# 9_USART_schdoc.net
KiCad netlist of a schematic drawn in Altium Designer
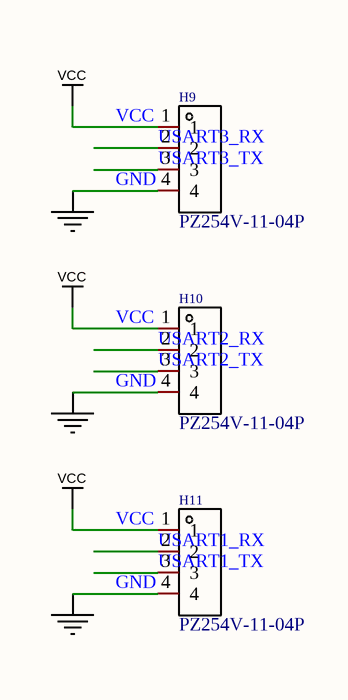
[diagram p0: 9_USART.schdoc.schdoc]

(export (version "E")
  (design (tool "Eeschema 10.0.6"))
  (components
    (comp (ref "H9")
      (value "PZ254V-11-04P")
      (fields (field (name "NAME") "PZ254V-11-04P") (field (name "MANUFACTURER") "XFCN(兴飞)"))
      (libsource (lib "altium-import") (part "root_0_PZ254V-11-04P_"))
    )
    (comp (ref "H10")
      (value "PZ254V-11-04P")
      (fields (field (name "NAME") "PZ254V-11-04P") (field (name "MANUFACTURER") "XFCN(兴飞)"))
      (libsource (lib "altium-import") (part "root_0_PZ254V-11-04P_"))
    )
    (comp (ref "H11")
      (value "PZ254V-11-04P")
      (fields (field (name "NAME") "PZ254V-11-04P") (field (name "MANUFACTURER") "XFCN(兴飞)"))
      (libsource (lib "altium-import") (part "root_0_PZ254V-11-04P_"))
    )
  )
  (nets
    (net (code "1") (name "/GND") (class "Default")
      (node (ref "H10") (pin "4") (pinfunction "4_4") (pintype "passive"))
      (node (ref "H11") (pin "4") (pinfunction "4_4") (pintype "passive"))
      (node (ref "H9") (pin "4") (pinfunction "4_4") (pintype "passive"))
    )
    (net (code "2") (name "/USART1_RX") (class "Default")
      (node (ref "H11") (pin "2") (pinfunction "2_2") (pintype "passive"))
    )
    (net (code "3") (name "/USART1_TX") (class "Default")
      (node (ref "H11") (pin "3") (pinfunction "3_3") (pintype "passive"))
    )
    (net (code "4") (name "/USART2_RX") (class "Default")
      (node (ref "H10") (pin "2") (pinfunction "2_2") (pintype "passive"))
    )
    (net (code "5") (name "/USART2_TX") (class "Default")
      (node (ref "H10") (pin "3") (pinfunction "3_3") (pintype "passive"))
    )
    (net (code "6") (name "/USART3_RX") (class "Default")
      (node (ref "H9") (pin "2") (pinfunction "2_2") (pintype "passive"))
    )
    (net (code "7") (name "/USART3_TX") (class "Default")
      (node (ref "H9") (pin "3") (pinfunction "3_3") (pintype "passive"))
    )
    (net (code "8") (name "VCC") (class "Default")
      (node (ref "H10") (pin "1") (pinfunction "1_1") (pintype "passive"))
      (node (ref "H11") (pin "1") (pinfunction "1_1") (pintype "passive"))
      (node (ref "H9") (pin "1") (pinfunction "1_1") (pintype "passive"))
    )
  )
)
